# Adafruit_Terminal_FeatherWing.net
KiCad netlist of a schematic drawn in EAGLE
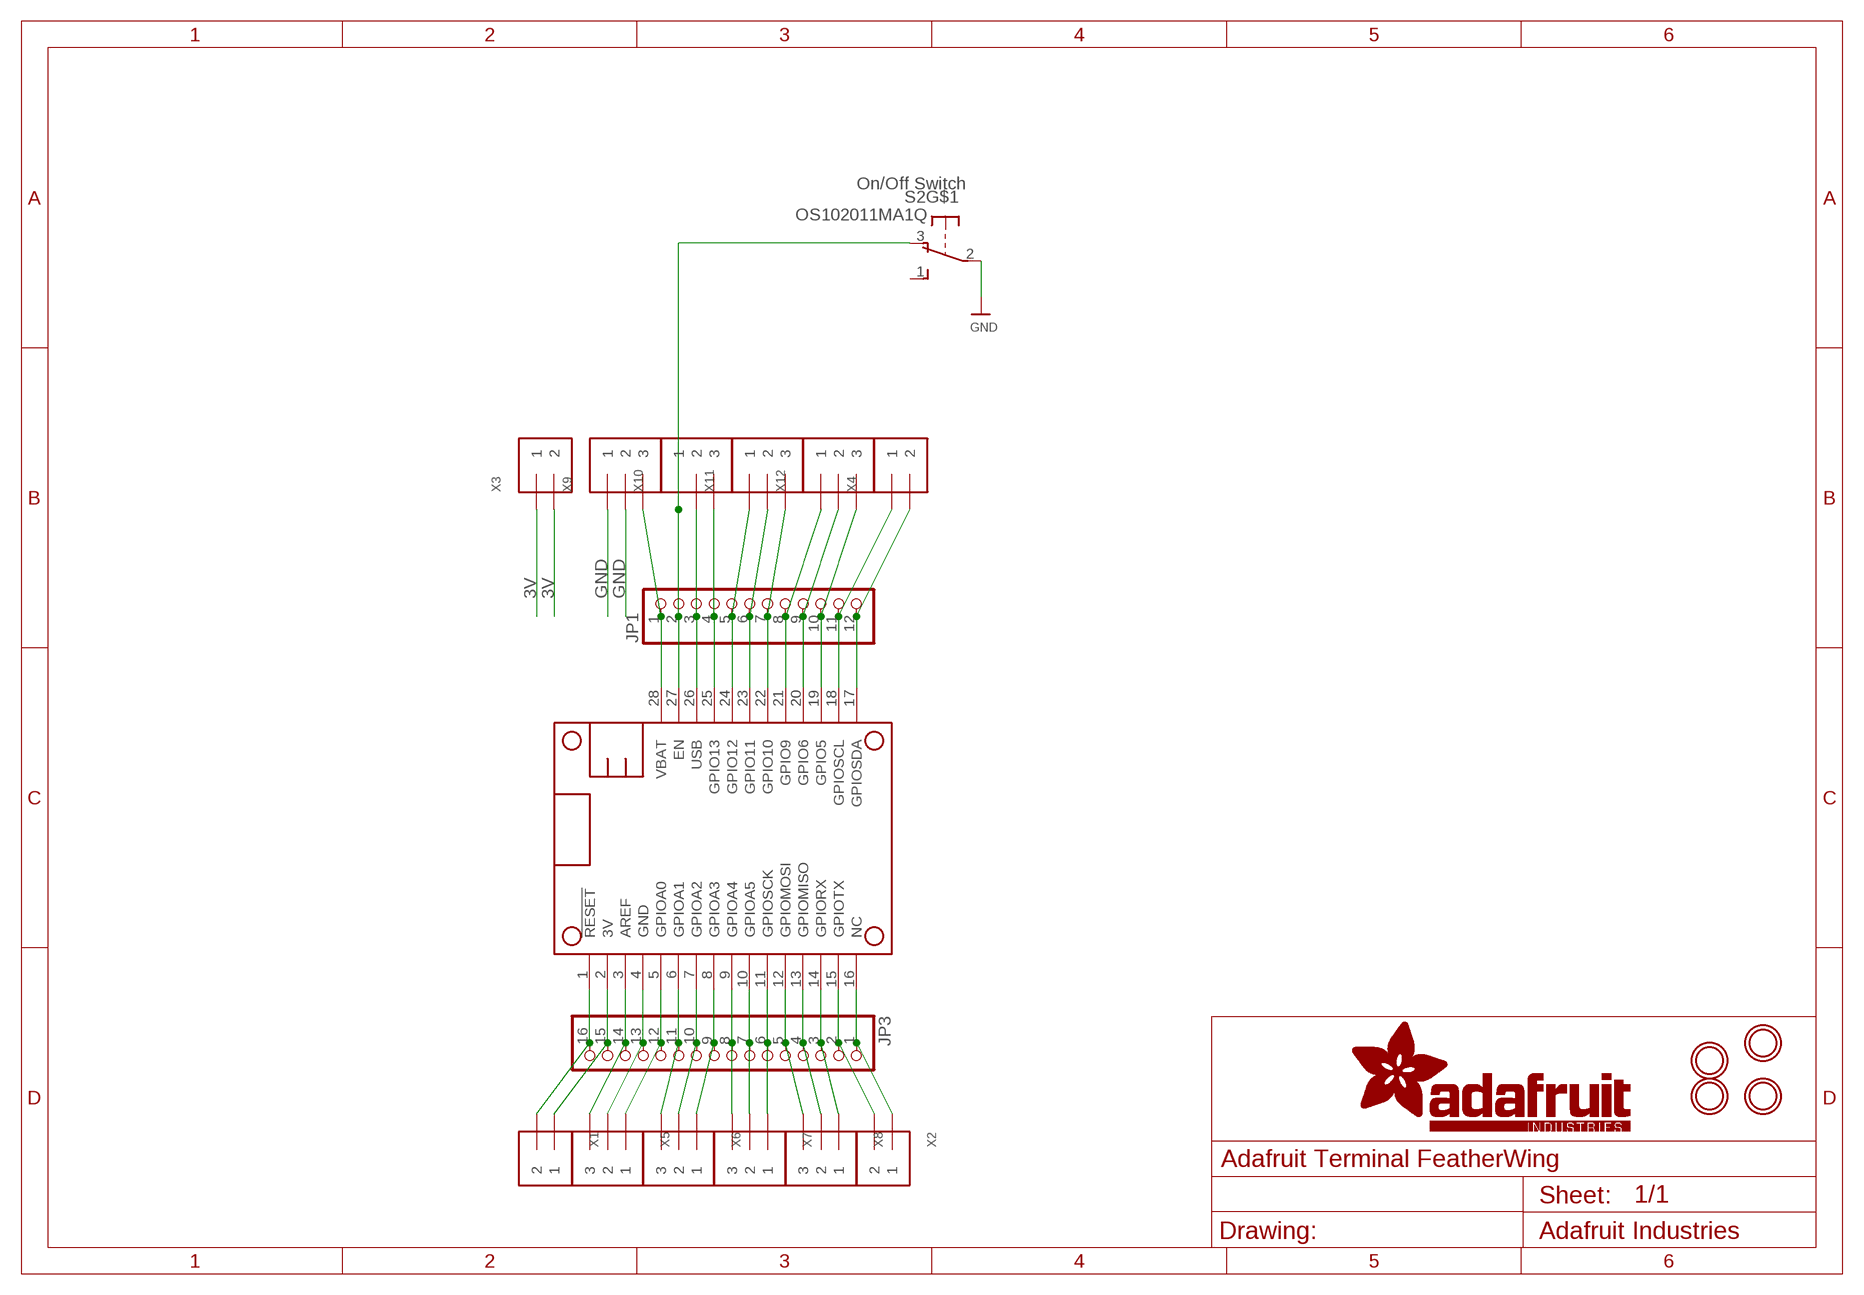
[diagram p0: schematic, sheet 1]

(export (version "E")
  (design (tool "Eeschema 10.0.6"))
  (components
    (comp (ref "JP1")
      (value "HEADER-1X1276MIL")
      (footprint "eagle-import:1X12_ROUND_76MIL")
      (libsource (lib "eagle-import") (part "HEADER-1X1276MIL"))
    )
    (comp (ref "JP3")
      (value "HEADER-1X16_76MIL")
      (footprint "eagle-import:1X16_ROUND_76MIL")
      (libsource (lib "eagle-import") (part "HEADER-1X16_76MIL"))
    )
    (comp (ref "MS1")
      (value "FEATHERWING_NODIM")
      (footprint "eagle-import:FEATHERWING_DIM")
      (libsource (lib "eagle-import") (part "FEATHERWING_NODIM"))
    )
    (comp (ref "S2")
      (value "OS102011MA1Q")
      (footprint "eagle-import:OS102011MA1Q")
      (libsource (lib "eagle-import") (part "OS102011MA1Q"))
    )
    (comp (ref "U$2")
      (value "MOUNTINGHOLE3.0THIN")
      (footprint "eagle-import:MOUNTINGHOLE_3.0_PLATEDTHIN")
      (libsource (lib "eagle-import") (part "MOUNTINGHOLE3.0THIN"))
    )
    (comp (ref "U$3")
      (value "MOUNTINGHOLE3.0THIN")
      (footprint "eagle-import:MOUNTINGHOLE_3.0_PLATEDTHIN")
      (libsource (lib "eagle-import") (part "MOUNTINGHOLE3.0THIN"))
    )
    (comp (ref "U$4")
      (value "MOUNTINGHOLE3.0THIN")
      (footprint "eagle-import:MOUNTINGHOLE_3.0_PLATEDTHIN")
      (libsource (lib "eagle-import") (part "MOUNTINGHOLE3.0THIN"))
    )
    (comp (ref "U$5")
      (value "MOUNTINGHOLE3.0THIN")
      (footprint "eagle-import:MOUNTINGHOLE_3.0_PLATEDTHIN")
      (libsource (lib "eagle-import") (part "MOUNTINGHOLE3.0THIN"))
    )
    (comp (ref "X1")
      (value "TERMBLOCK_1X2")
      (footprint "eagle-import:TERMBLOCK_1X2-3.5MM")
      (libsource (lib "eagle-import") (part "TERMBLOCK_1X2"))
    )
    (comp (ref "X2")
      (value "TERMBLOCK_1X2")
      (footprint "eagle-import:TERMBLOCK_1X2-3.5MM")
      (libsource (lib "eagle-import") (part "TERMBLOCK_1X2"))
    )
    (comp (ref "X3")
      (value "TERMBLOCK_1X2")
      (footprint "eagle-import:TERMBLOCK_1X2-3.5MM")
      (libsource (lib "eagle-import") (part "TERMBLOCK_1X2"))
    )
    (comp (ref "X4")
      (value "TERMBLOCK_1X2")
      (footprint "eagle-import:TERMBLOCK_1X2-3.5MM")
      (libsource (lib "eagle-import") (part "TERMBLOCK_1X2"))
    )
    (comp (ref "X5")
      (value "TERMBLOCK_1X3")
      (footprint "eagle-import:TERMBLOCK_1X3-3.5MM")
      (libsource (lib "eagle-import") (part "TERMBLOCK_1X3"))
    )
    (comp (ref "X6")
      (value "TERMBLOCK_1X3")
      (footprint "eagle-import:TERMBLOCK_1X3-3.5MM")
      (libsource (lib "eagle-import") (part "TERMBLOCK_1X3"))
    )
    (comp (ref "X7")
      (value "TERMBLOCK_1X3")
      (footprint "eagle-import:TERMBLOCK_1X3-3.5MM")
      (libsource (lib "eagle-import") (part "TERMBLOCK_1X3"))
    )
    (comp (ref "X8")
      (value "TERMBLOCK_1X3")
      (footprint "eagle-import:TERMBLOCK_1X3-3.5MM")
      (libsource (lib "eagle-import") (part "TERMBLOCK_1X3"))
    )
    (comp (ref "X9")
      (value "TERMBLOCK_1X3")
      (footprint "eagle-import:TERMBLOCK_1X3-3.5MM")
      (libsource (lib "eagle-import") (part "TERMBLOCK_1X3"))
    )
    (comp (ref "X10")
      (value "TERMBLOCK_1X3")
      (footprint "eagle-import:TERMBLOCK_1X3-3.5MM")
      (libsource (lib "eagle-import") (part "TERMBLOCK_1X3"))
    )
    (comp (ref "X11")
      (value "TERMBLOCK_1X3")
      (footprint "eagle-import:TERMBLOCK_1X3-3.5MM")
      (libsource (lib "eagle-import") (part "TERMBLOCK_1X3"))
    )
    (comp (ref "X12")
      (value "TERMBLOCK_1X3")
      (footprint "eagle-import:TERMBLOCK_1X3-3.5MM")
      (libsource (lib "eagle-import") (part "TERMBLOCK_1X3"))
    )
  )
  (nets
    (net (code "1") (name "/3V") (class "Default")
      (node (ref "JP3") (pin "15") (pinfunction "15_15") (pintype "passive"))
      (node (ref "MS1") (pin "2") (pinfunction "3V_2") (pintype "power_in"))
      (node (ref "X1") (pin "1") (pinfunction "1_1") (pintype "passive"))
      (node (ref "X3") (pin "1") (pinfunction "1_1") (pintype "passive"))
      (node (ref "X3") (pin "2") (pinfunction "2_2") (pintype "passive"))
    )
    (net (code "2") (name "GND") (class "Default")
      (node (ref "JP3") (pin "13") (pinfunction "13_13") (pintype "passive"))
      (node (ref "MS1") (pin "4") (pinfunction "GND_4") (pintype "power_in"))
      (node (ref "S2") (pin "2") (pinfunction "P_2") (pintype "passive"))
      (node (ref "X5") (pin "2") (pinfunction "2_2") (pintype "passive"))
      (node (ref "X9") (pin "1") (pinfunction "1_1") (pintype "passive"))
      (node (ref "X9") (pin "2") (pinfunction "2_2") (pintype "passive"))
    )
    (net (code "3") (name "Net-(MS1-AREF)") (class "Default")
      (node (ref "JP3") (pin "14") (pinfunction "14_14") (pintype "passive"))
      (node (ref "MS1") (pin "3") (pinfunction "AREF_3") (pintype "passive"))
      (node (ref "X5") (pin "3") (pinfunction "3_3") (pintype "passive"))
    )
    (net (code "4") (name "Net-(MS1-EN)") (class "Default")
      (node (ref "JP1") (pin "2") (pinfunction "2_2") (pintype "passive"))
      (node (ref "MS1") (pin "27") (pinfunction "EN_27") (pintype "passive"))
      (node (ref "S2") (pin "3") (pinfunction "O_3") (pintype "passive"))
      (node (ref "X10") (pin "1") (pinfunction "1_1") (pintype "passive"))
    )
    (net (code "5") (name "Net-(MS1-GPIO5)") (class "Default")
      (node (ref "JP1") (pin "10") (pinfunction "10_10") (pintype "passive"))
      (node (ref "MS1") (pin "19") (pinfunction "GPIO5_19") (pintype "bidirectional"))
      (node (ref "X12") (pin "3") (pinfunction "3_3") (pintype "passive"))
    )
    (net (code "6") (name "Net-(MS1-GPIO6)") (class "Default")
      (node (ref "JP1") (pin "9") (pinfunction "9_9") (pintype "passive"))
      (node (ref "MS1") (pin "20") (pinfunction "GPIO6_20") (pintype "bidirectional"))
      (node (ref "X12") (pin "2") (pinfunction "2_2") (pintype "passive"))
    )
    (net (code "7") (name "Net-(MS1-GPIO9)") (class "Default")
      (node (ref "JP1") (pin "8") (pinfunction "8_8") (pintype "passive"))
      (node (ref "MS1") (pin "21") (pinfunction "GPIO9_21") (pintype "bidirectional"))
      (node (ref "X12") (pin "1") (pinfunction "1_1") (pintype "passive"))
    )
    (net (code "8") (name "Net-(MS1-GPIO10)") (class "Default")
      (node (ref "JP1") (pin "7") (pinfunction "7_7") (pintype "passive"))
      (node (ref "MS1") (pin "22") (pinfunction "GPIO10_22") (pintype "bidirectional"))
      (node (ref "X11") (pin "3") (pinfunction "3_3") (pintype "passive"))
    )
    (net (code "9") (name "Net-(MS1-GPIO11)") (class "Default")
      (node (ref "JP1") (pin "6") (pinfunction "6_6") (pintype "passive"))
      (node (ref "MS1") (pin "23") (pinfunction "GPIO11_23") (pintype "bidirectional"))
      (node (ref "X11") (pin "2") (pinfunction "2_2") (pintype "passive"))
    )
    (net (code "10") (name "Net-(MS1-GPIO12)") (class "Default")
      (node (ref "JP1") (pin "5") (pinfunction "5_5") (pintype "passive"))
      (node (ref "MS1") (pin "24") (pinfunction "GPIO12_24") (pintype "bidirectional"))
      (node (ref "X11") (pin "1") (pinfunction "1_1") (pintype "passive"))
    )
    (net (code "11") (name "Net-(MS1-GPIO13)") (class "Default")
      (node (ref "JP1") (pin "4") (pinfunction "4_4") (pintype "passive"))
      (node (ref "MS1") (pin "25") (pinfunction "GPIO13_25") (pintype "bidirectional"))
      (node (ref "X10") (pin "3") (pinfunction "3_3") (pintype "passive"))
    )
    (net (code "12") (name "Net-(MS1-GPIOA0)") (class "Default")
      (node (ref "JP3") (pin "12") (pinfunction "12_12") (pintype "passive"))
      (node (ref "MS1") (pin "5") (pinfunction "GPIOA0_5") (pintype "bidirectional"))
      (node (ref "X5") (pin "1") (pinfunction "1_1") (pintype "passive"))
    )
    (net (code "13") (name "Net-(MS1-GPIOA1)") (class "Default")
      (node (ref "JP3") (pin "11") (pinfunction "11_11") (pintype "passive"))
      (node (ref "MS1") (pin "6") (pinfunction "GPIOA1_6") (pintype "bidirectional"))
      (node (ref "X6") (pin "3") (pinfunction "3_3") (pintype "passive"))
    )
    (net (code "14") (name "Net-(MS1-GPIOA2)") (class "Default")
      (node (ref "JP3") (pin "10") (pinfunction "10_10") (pintype "passive"))
      (node (ref "MS1") (pin "7") (pinfunction "GPIOA2_7") (pintype "bidirectional"))
      (node (ref "X6") (pin "2") (pinfunction "2_2") (pintype "passive"))
    )
    (net (code "15") (name "Net-(MS1-GPIOA3)") (class "Default")
      (node (ref "JP3") (pin "9") (pinfunction "9_9") (pintype "passive"))
      (node (ref "MS1") (pin "8") (pinfunction "GPIOA3_8") (pintype "bidirectional"))
      (node (ref "X6") (pin "1") (pinfunction "1_1") (pintype "passive"))
    )
    (net (code "16") (name "Net-(MS1-GPIOA4)") (class "Default")
      (node (ref "JP3") (pin "8") (pinfunction "8_8") (pintype "passive"))
      (node (ref "MS1") (pin "9") (pinfunction "GPIOA4_9") (pintype "bidirectional"))
      (node (ref "X7") (pin "3") (pinfunction "3_3") (pintype "passive"))
    )
    (net (code "17") (name "Net-(MS1-GPIOA5)") (class "Default")
      (node (ref "JP3") (pin "7") (pinfunction "7_7") (pintype "passive"))
      (node (ref "MS1") (pin "10") (pinfunction "GPIOA5_10") (pintype "bidirectional"))
      (node (ref "X7") (pin "2") (pinfunction "2_2") (pintype "passive"))
    )
    (net (code "18") (name "Net-(MS1-GPIOMISO)") (class "Default")
      (node (ref "JP3") (pin "4") (pinfunction "4_4") (pintype "passive"))
      (node (ref "MS1") (pin "13") (pinfunction "GPIOMISO_13") (pintype "bidirectional"))
      (node (ref "X8") (pin "2") (pinfunction "2_2") (pintype "passive"))
    )
    (net (code "19") (name "Net-(MS1-GPIOMOSI)") (class "Default")
      (node (ref "JP3") (pin "5") (pinfunction "5_5") (pintype "passive"))
      (node (ref "MS1") (pin "12") (pinfunction "GPIOMOSI_12") (pintype "bidirectional"))
      (node (ref "X8") (pin "3") (pinfunction "3_3") (pintype "passive"))
    )
    (net (code "20") (name "Net-(MS1-GPIORX)") (class "Default")
      (node (ref "JP3") (pin "3") (pinfunction "3_3") (pintype "passive"))
      (node (ref "MS1") (pin "14") (pinfunction "GPIORX_14") (pintype "bidirectional"))
      (node (ref "X8") (pin "1") (pinfunction "1_1") (pintype "passive"))
    )
    (net (code "21") (name "Net-(MS1-GPIOSCK)") (class "Default")
      (node (ref "JP3") (pin "6") (pinfunction "6_6") (pintype "passive"))
      (node (ref "MS1") (pin "11") (pinfunction "GPIOSCK_11") (pintype "bidirectional"))
      (node (ref "X7") (pin "1") (pinfunction "1_1") (pintype "passive"))
    )
    (net (code "22") (name "Net-(MS1-GPIOSCL)") (class "Default")
      (node (ref "JP1") (pin "11") (pinfunction "11_11") (pintype "passive"))
      (node (ref "MS1") (pin "18") (pinfunction "GPIOSCL_18") (pintype "bidirectional"))
      (node (ref "X4") (pin "1") (pinfunction "1_1") (pintype "passive"))
    )
    (net (code "23") (name "Net-(MS1-GPIOSDA)") (class "Default")
      (node (ref "JP1") (pin "12") (pinfunction "12_12") (pintype "passive"))
      (node (ref "MS1") (pin "17") (pinfunction "GPIOSDA_17") (pintype "bidirectional"))
      (node (ref "X4") (pin "2") (pinfunction "2_2") (pintype "passive"))
    )
    (net (code "24") (name "Net-(MS1-GPIOTX)") (class "Default")
      (node (ref "JP3") (pin "2") (pinfunction "2_2") (pintype "passive"))
      (node (ref "MS1") (pin "15") (pinfunction "GPIOTX_15") (pintype "bidirectional"))
      (node (ref "X2") (pin "2") (pinfunction "2_2") (pintype "passive"))
    )
    (net (code "25") (name "Net-(MS1-NC)") (class "Default")
      (node (ref "JP3") (pin "1") (pinfunction "1_1") (pintype "passive"))
      (node (ref "MS1") (pin "16") (pinfunction "NC_16") (pintype "passive"))
      (node (ref "X2") (pin "1") (pinfunction "1_1") (pintype "passive"))
    )
    (net (code "26") (name "Net-(MS1-USB)") (class "Default")
      (node (ref "JP1") (pin "3") (pinfunction "3_3") (pintype "passive"))
      (node (ref "MS1") (pin "26") (pinfunction "USB_26") (pintype "power_in"))
      (node (ref "X10") (pin "2") (pinfunction "2_2") (pintype "passive"))
    )
    (net (code "27") (name "Net-(MS1-VBAT)") (class "Default")
      (node (ref "JP1") (pin "1") (pinfunction "1_1") (pintype "passive"))
      (node (ref "MS1") (pin "28") (pinfunction "VBAT_28") (pintype "power_in"))
      (node (ref "X9") (pin "3") (pinfunction "3_3") (pintype "passive"))
    )
    (net (code "28") (name "Net-(MS1-~{RESET})") (class "Default")
      (node (ref "JP3") (pin "16") (pinfunction "16_16") (pintype "passive"))
      (node (ref "MS1") (pin "1") (pinfunction "~{RESET}_1") (pintype "input"))
      (node (ref "X1") (pin "2") (pinfunction "2_2") (pintype "passive"))
    )
    (net (code "29") (name "unconnected-(S2A-S-Pad1)") (class "Default")
      (node (ref "S2") (pin "1") (pinfunction "S_1") (pintype "passive"))
    )
  )
)
